# pulse_sensor.net
KiCad netlist of a schematic drawn in EAGLE
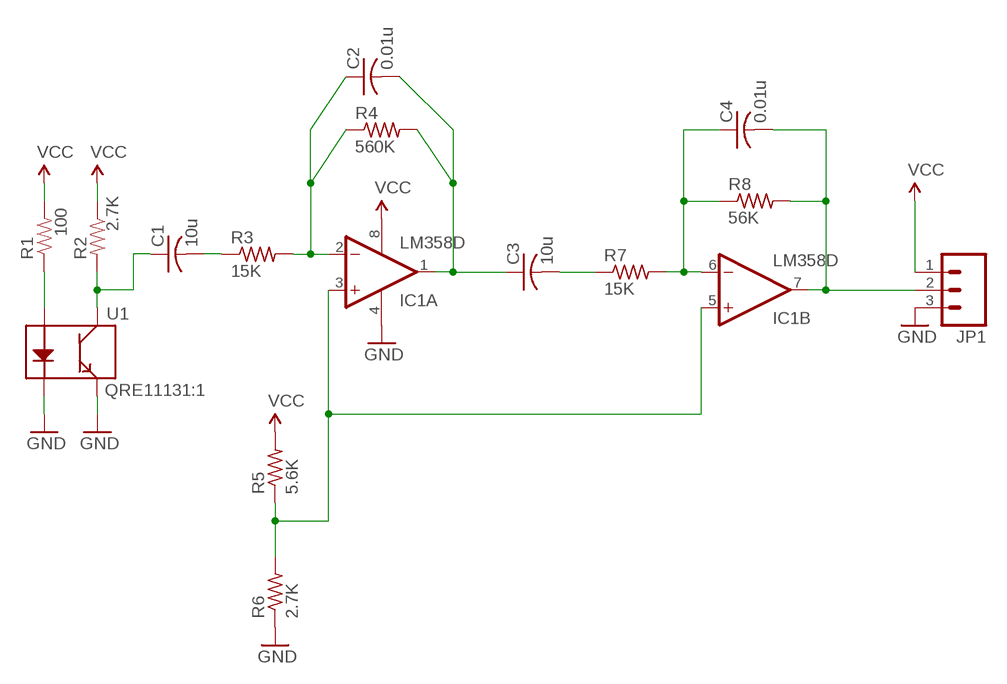
[diagram p0: schematic, sheet 1]

(export (version "E")
  (design (tool "Eeschema 10.0.6"))
  (components
    (comp (ref "C1")
      (value "10u")
      (footprint "eagle-import:C0603")
      (libsource (lib "eagle-import") (part "C-USC0603"))
    )
    (comp (ref "C2")
      (value "0.01u")
      (footprint "eagle-import:C0603")
      (libsource (lib "eagle-import") (part "C-USC0603"))
    )
    (comp (ref "C3")
      (value "10u")
      (footprint "eagle-import:C0603")
      (libsource (lib "eagle-import") (part "C-USC0603"))
    )
    (comp (ref "C4")
      (value "0.01u")
      (footprint "eagle-import:C0603")
      (libsource (lib "eagle-import") (part "C-USC0603"))
    )
    (comp (ref "IC1")
      (value "LM358D")
      (footprint "eagle-import:SO08")
      (libsource (lib "eagle-import") (part "LM358D"))
    )
    (comp (ref "JP1")
      (value "M03PTH")
      (footprint "eagle-import:1X03")
      (libsource (lib "eagle-import") (part "M03PTH"))
    )
    (comp (ref "R1")
      (value "100")
      (footprint "eagle-import:0603-RES")
      (libsource (lib "eagle-import") (part "RESISTOR0603-RES"))
    )
    (comp (ref "R2")
      (value "2.7K")
      (footprint "eagle-import:0603-RES")
      (libsource (lib "eagle-import") (part "RESISTOR0603-RES"))
    )
    (comp (ref "R3")
      (value "15K")
      (footprint "eagle-import:R0603")
      (libsource (lib "eagle-import") (part "R-US_R0603"))
    )
    (comp (ref "R4")
      (value "560K")
      (footprint "eagle-import:R0603")
      (libsource (lib "eagle-import") (part "R-US_R0603"))
    )
    (comp (ref "R5")
      (value "5.6K")
      (footprint "eagle-import:R0603")
      (libsource (lib "eagle-import") (part "R-US_R0603"))
    )
    (comp (ref "R6")
      (value "2.7K")
      (footprint "eagle-import:R0603")
      (libsource (lib "eagle-import") (part "R-US_R0603"))
    )
    (comp (ref "R7")
      (value "15K")
      (footprint "eagle-import:R0603")
      (libsource (lib "eagle-import") (part "R-US_R0603"))
    )
    (comp (ref "R8")
      (value "56K")
      (footprint "eagle-import:R0603")
      (libsource (lib "eagle-import") (part "R-US_R0603"))
    )
    (comp (ref "U1")
      (value "QRE11131:1")
      (footprint "eagle-import:QRE1113-1_1")
      (libsource (lib "eagle-import") (part "QRE11131{colon}1"))
    )
  )
  (nets
    (net (code "1") (name "GND") (class "Default")
      (node (ref "IC1") (pin "4") (pinfunction "V-_4") (pintype "power_in"))
      (node (ref "JP1") (pin "3") (pinfunction "3_3") (pintype "passive"))
      (node (ref "R6") (pin "1") (pinfunction "1_1") (pintype "passive"))
      (node (ref "U1") (pin "2") (pinfunction "K_2") (pintype "bidirectional"))
      (node (ref "U1") (pin "4") (pinfunction "E_4") (pintype "bidirectional"))
    )
    (net (code "2") (name "Net-(C1-Pad2)") (class "Default")
      (node (ref "C1") (pin "2") (pinfunction "2_2") (pintype "passive"))
      (node (ref "R3") (pin "1") (pinfunction "1_1") (pintype "passive"))
    )
    (net (code "3") (name "Net-(C3-Pad2)") (class "Default")
      (node (ref "C3") (pin "2") (pinfunction "2_2") (pintype "passive"))
      (node (ref "R7") (pin "1") (pinfunction "1_1") (pintype "passive"))
    )
    (net (code "4") (name "Net-(IC1A-+IN)") (class "Default")
      (node (ref "IC1") (pin "3") (pinfunction "+IN_3") (pintype "input"))
      (node (ref "IC1") (pin "5") (pinfunction "+IN_5") (pintype "input"))
      (node (ref "R5") (pin "1") (pinfunction "1_1") (pintype "passive"))
      (node (ref "R6") (pin "2") (pinfunction "2_2") (pintype "passive"))
    )
    (net (code "5") (name "Net-(IC1A--IN)") (class "Default")
      (node (ref "C2") (pin "1") (pinfunction "1_1") (pintype "passive"))
      (node (ref "IC1") (pin "2") (pinfunction "-IN_2") (pintype "input"))
      (node (ref "R3") (pin "2") (pinfunction "2_2") (pintype "passive"))
      (node (ref "R4") (pin "1") (pinfunction "1_1") (pintype "passive"))
    )
    (net (code "6") (name "Net-(IC1A-OUT)") (class "Default")
      (node (ref "C2") (pin "2") (pinfunction "2_2") (pintype "passive"))
      (node (ref "C3") (pin "1") (pinfunction "1_1") (pintype "passive"))
      (node (ref "IC1") (pin "1") (pinfunction "OUT_1") (pintype "output"))
      (node (ref "R4") (pin "2") (pinfunction "2_2") (pintype "passive"))
    )
    (net (code "7") (name "Net-(IC1B--IN)") (class "Default")
      (node (ref "C4") (pin "1") (pinfunction "1_1") (pintype "passive"))
      (node (ref "IC1") (pin "6") (pinfunction "-IN_6") (pintype "input"))
      (node (ref "R7") (pin "2") (pinfunction "2_2") (pintype "passive"))
      (node (ref "R8") (pin "1") (pinfunction "1_1") (pintype "passive"))
    )
    (net (code "8") (name "Net-(IC1B-OUT)") (class "Default")
      (node (ref "C4") (pin "2") (pinfunction "2_2") (pintype "passive"))
      (node (ref "IC1") (pin "7") (pinfunction "OUT_7") (pintype "output"))
      (node (ref "JP1") (pin "2") (pinfunction "2_2") (pintype "passive"))
      (node (ref "R8") (pin "2") (pinfunction "2_2") (pintype "passive"))
    )
    (net (code "9") (name "Net-(U1-A)") (class "Default")
      (node (ref "R1") (pin "1") (pinfunction "1_1") (pintype "passive"))
      (node (ref "U1") (pin "1") (pinfunction "A_1") (pintype "bidirectional"))
    )
    (net (code "10") (name "Net-(U1-C)") (class "Default")
      (node (ref "C1") (pin "1") (pinfunction "1_1") (pintype "passive"))
      (node (ref "R2") (pin "2") (pinfunction "2_2") (pintype "passive"))
      (node (ref "U1") (pin "3") (pinfunction "C_3") (pintype "bidirectional"))
    )
    (net (code "11") (name "VCC") (class "Default")
      (node (ref "IC1") (pin "8") (pinfunction "V+_8") (pintype "power_in"))
      (node (ref "JP1") (pin "1") (pinfunction "1_1") (pintype "passive"))
      (node (ref "R1") (pin "2") (pinfunction "2_2") (pintype "passive"))
      (node (ref "R2") (pin "1") (pinfunction "1_1") (pintype "passive"))
      (node (ref "R5") (pin "2") (pinfunction "2_2") (pintype "passive"))
    )
  )
)
